# AetherMesh_interface_to_TI_SmartRF06EB_M.net
KiCad netlist of a schematic drawn in EAGLE
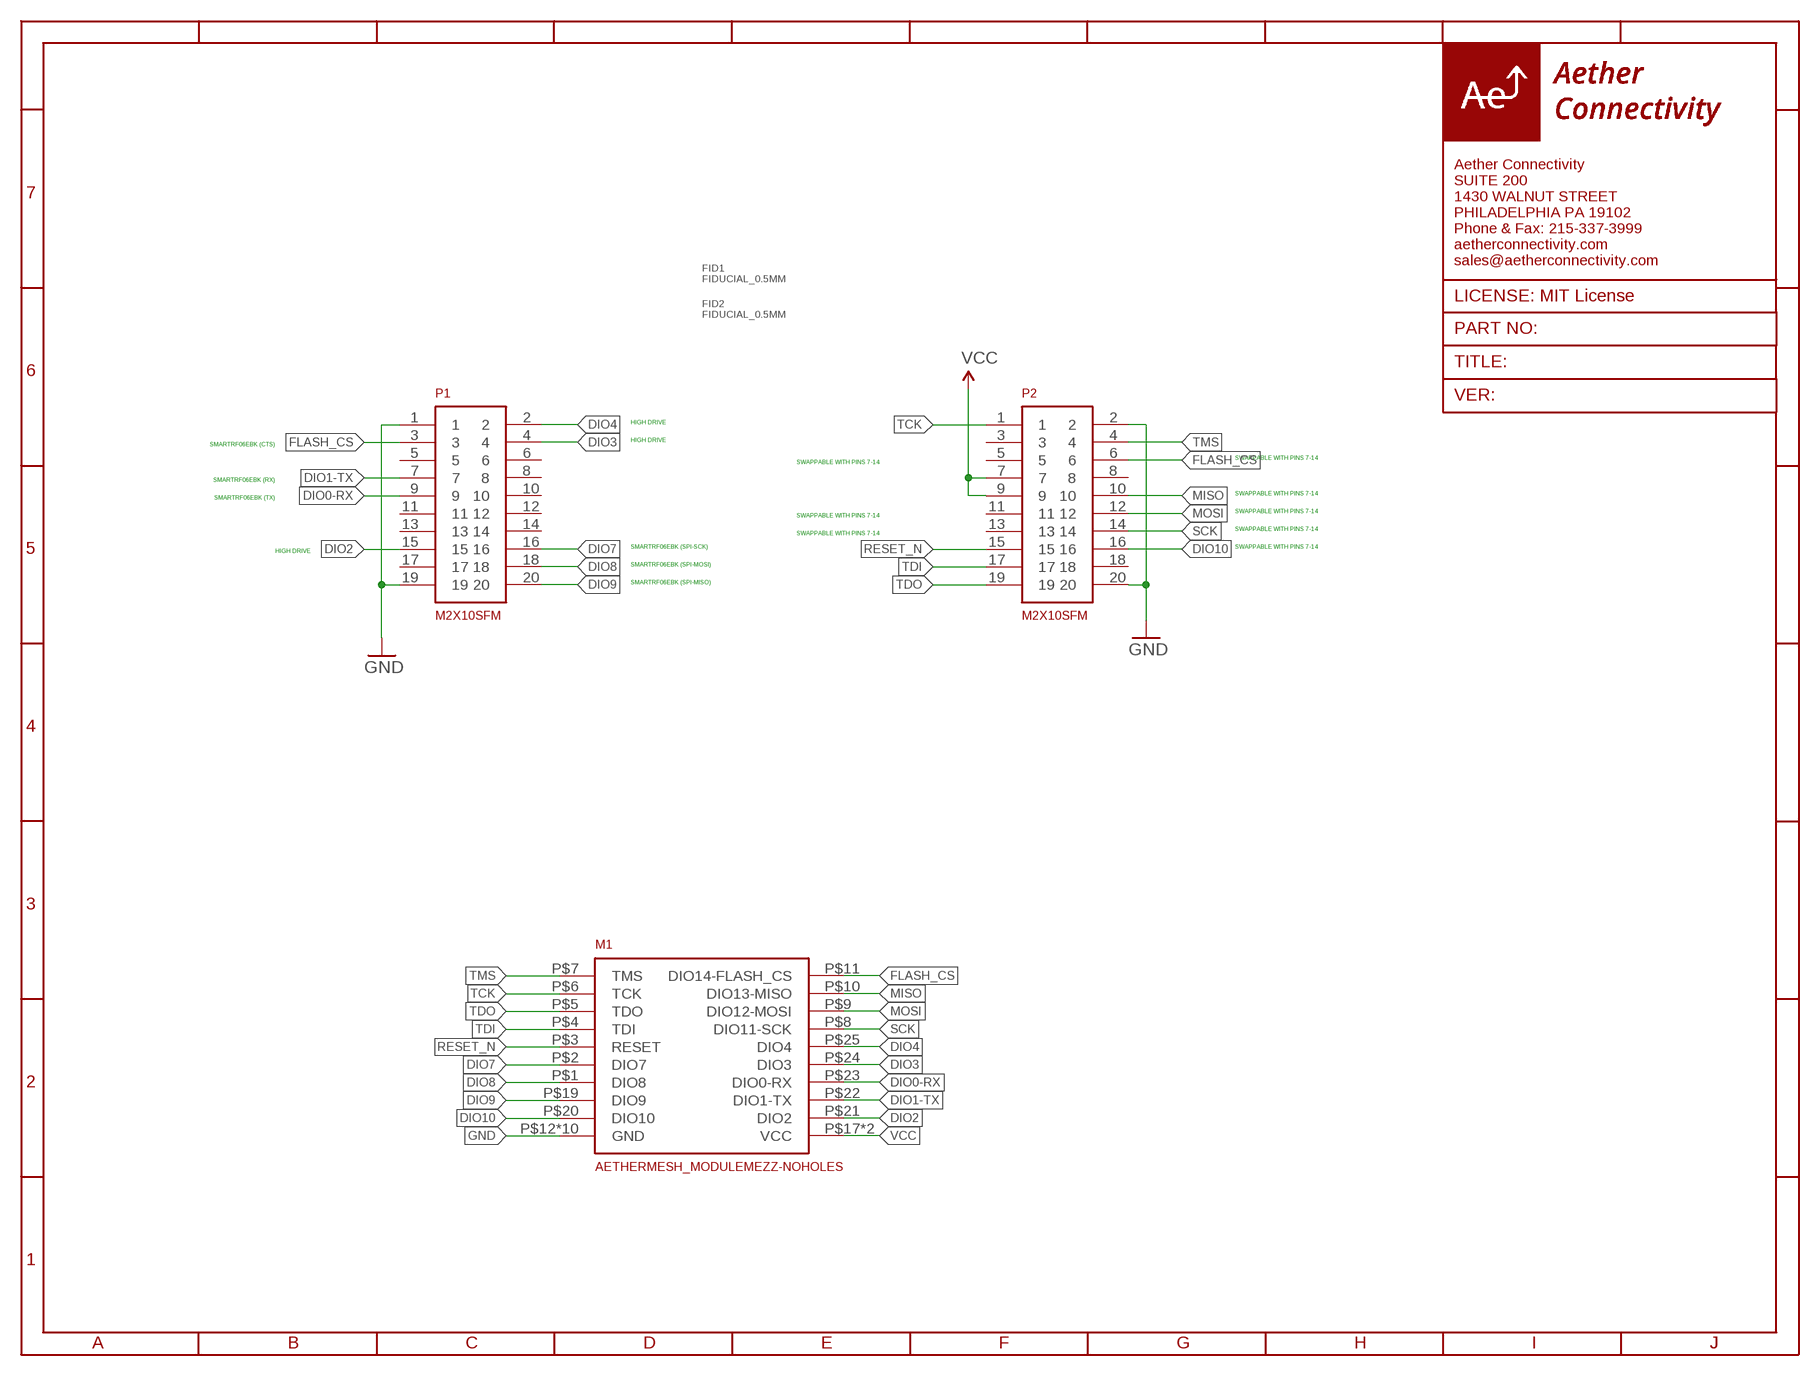
[diagram p0: schematic, sheet 1]

(export (version "E")
  (design (tool "Eeschema 10.0.6"))
  (components
    (comp (ref "FID1")
      (value "FIDUCIAL_0.5MM")
      (footprint "eagle-import:FIDUCIAL_0.5MM")
      (libsource (lib "eagle-import") (part "FIDUCIAL_0.5MM"))
    )
    (comp (ref "FID2")
      (value "FIDUCIAL_0.5MM")
      (footprint "eagle-import:FIDUCIAL_0.5MM")
      (libsource (lib "eagle-import") (part "FIDUCIAL_0.5MM"))
    )
    (comp (ref "M1")
      (value "AETHERMESH_MODULEMEZZ-NOHOLES")
      (footprint "eagle-import:AETHERMESH_MEZZ_MOUNT_NOHOLES")
      (libsource (lib "eagle-import") (part "AETHERMESH_MODULEMEZZ-NOHOLES"))
    )
    (comp (ref "P1")
      (value "M2X10SFM")
      (footprint "eagle-import:2X10_SFM-110-02-S-D-A-K-TR")
      (libsource (lib "eagle-import") (part "M2X10SFM"))
    )
    (comp (ref "P2")
      (value "M2X10SFM")
      (footprint "eagle-import:2X10_SFM-110-02-S-D-A-K-TR")
      (libsource (lib "eagle-import") (part "M2X10SFM"))
    )
  )
  (nets
    (net (code "1") (name "DIO0-RX") (class "Default")
      (node (ref "M1") (pin "P$23") (pinfunction "DIO0-RX_P$23") (pintype "bidirectional"))
      (node (ref "P1") (pin "9") (pinfunction "9_9") (pintype "bidirectional"))
    )
    (net (code "2") (name "DIO1-TX") (class "Default")
      (node (ref "M1") (pin "P$22") (pinfunction "DIO1-TX_P$22") (pintype "bidirectional"))
      (node (ref "P1") (pin "7") (pinfunction "7_7") (pintype "bidirectional"))
    )
    (net (code "3") (name "DIO2") (class "Default")
      (node (ref "M1") (pin "P$21") (pinfunction "DIO2_P$21") (pintype "bidirectional"))
      (node (ref "P1") (pin "15") (pinfunction "15_15") (pintype "bidirectional"))
    )
    (net (code "4") (name "DIO3") (class "Default")
      (node (ref "M1") (pin "P$24") (pinfunction "DIO3_P$24") (pintype "bidirectional"))
      (node (ref "P1") (pin "4") (pinfunction "4_4") (pintype "bidirectional"))
    )
    (net (code "5") (name "DIO4") (class "Default")
      (node (ref "M1") (pin "P$25") (pinfunction "DIO4_P$25") (pintype "bidirectional"))
      (node (ref "P1") (pin "2") (pinfunction "2_2") (pintype "bidirectional"))
    )
    (net (code "6") (name "DIO7") (class "Default")
      (node (ref "M1") (pin "P$2") (pinfunction "DIO7_P$2") (pintype "bidirectional"))
      (node (ref "P1") (pin "16") (pinfunction "16_16") (pintype "bidirectional"))
    )
    (net (code "7") (name "DIO8") (class "Default")
      (node (ref "M1") (pin "P$1") (pinfunction "DIO8_P$1") (pintype "bidirectional"))
      (node (ref "P1") (pin "18") (pinfunction "18_18") (pintype "bidirectional"))
    )
    (net (code "8") (name "DIO9") (class "Default")
      (node (ref "M1") (pin "P$19") (pinfunction "DIO9_P$19") (pintype "bidirectional"))
      (node (ref "P1") (pin "20") (pinfunction "20_20") (pintype "bidirectional"))
    )
    (net (code "9") (name "DIO10") (class "Default")
      (node (ref "M1") (pin "P$20") (pinfunction "DIO10_P$20") (pintype "bidirectional"))
      (node (ref "P2") (pin "16") (pinfunction "16_16") (pintype "bidirectional"))
    )
    (net (code "10") (name "FLASH_CS") (class "Default")
      (node (ref "M1") (pin "P$11") (pinfunction "DIO14-FLASH_CS_P$11") (pintype "bidirectional"))
      (node (ref "P1") (pin "3") (pinfunction "3_3") (pintype "bidirectional"))
      (node (ref "P2") (pin "6") (pinfunction "6_6") (pintype "bidirectional"))
    )
    (net (code "11") (name "GND") (class "Default")
      (node (ref "M1") (pin "P$12") (pinfunction "GND_P$12") (pintype "bidirectional"))
      (node (ref "M1") (pin "P$13") (pinfunction "GND_P$13") (pintype "bidirectional"))
      (node (ref "M1") (pin "P$14") (pinfunction "GND_P$14") (pintype "bidirectional"))
      (node (ref "M1") (pin "P$15") (pinfunction "GND_P$15") (pintype "bidirectional"))
      (node (ref "M1") (pin "P$16") (pinfunction "GND_P$16") (pintype "bidirectional"))
      (node (ref "M1") (pin "P$26") (pinfunction "GND_P$26") (pintype "bidirectional"))
      (node (ref "M1") (pin "P$27") (pinfunction "GND_P$27") (pintype "bidirectional"))
      (node (ref "M1") (pin "P$28") (pinfunction "GND_P$28") (pintype "bidirectional"))
      (node (ref "M1") (pin "P$29") (pinfunction "GND_P$29") (pintype "bidirectional"))
      (node (ref "M1") (pin "P$30") (pinfunction "GND_P$30") (pintype "bidirectional"))
      (node (ref "P1") (pin "1") (pinfunction "1_1") (pintype "bidirectional"))
      (node (ref "P1") (pin "19") (pinfunction "19_19") (pintype "bidirectional"))
      (node (ref "P2") (pin "2") (pinfunction "2_2") (pintype "bidirectional"))
      (node (ref "P2") (pin "20") (pinfunction "20_20") (pintype "bidirectional"))
    )
    (net (code "12") (name "MISO") (class "Default")
      (node (ref "M1") (pin "P$10") (pinfunction "DIO13-MISO_P$10") (pintype "bidirectional"))
      (node (ref "P2") (pin "10") (pinfunction "10_10") (pintype "bidirectional"))
    )
    (net (code "13") (name "MOSI") (class "Default")
      (node (ref "M1") (pin "P$9") (pinfunction "DIO12-MOSI_P$9") (pintype "bidirectional"))
      (node (ref "P2") (pin "12") (pinfunction "12_12") (pintype "bidirectional"))
    )
    (net (code "14") (name "RESET_N") (class "Default")
      (node (ref "M1") (pin "P$3") (pinfunction "RESET_P$3") (pintype "bidirectional"))
      (node (ref "P2") (pin "15") (pinfunction "15_15") (pintype "bidirectional"))
    )
    (net (code "15") (name "SCK") (class "Default")
      (node (ref "M1") (pin "P$8") (pinfunction "DIO11-SCK_P$8") (pintype "bidirectional"))
      (node (ref "P2") (pin "14") (pinfunction "14_14") (pintype "bidirectional"))
    )
    (net (code "16") (name "TCK") (class "Default")
      (node (ref "M1") (pin "P$6") (pinfunction "TCK_P$6") (pintype "bidirectional"))
      (node (ref "P2") (pin "1") (pinfunction "1_1") (pintype "bidirectional"))
    )
    (net (code "17") (name "TDI") (class "Default")
      (node (ref "M1") (pin "P$4") (pinfunction "TDI_P$4") (pintype "bidirectional"))
      (node (ref "P2") (pin "17") (pinfunction "17_17") (pintype "bidirectional"))
    )
    (net (code "18") (name "TDO") (class "Default")
      (node (ref "M1") (pin "P$5") (pinfunction "TDO_P$5") (pintype "bidirectional"))
      (node (ref "P2") (pin "19") (pinfunction "19_19") (pintype "bidirectional"))
    )
    (net (code "19") (name "TMS") (class "Default")
      (node (ref "M1") (pin "P$7") (pinfunction "TMS_P$7") (pintype "bidirectional"))
      (node (ref "P2") (pin "4") (pinfunction "4_4") (pintype "bidirectional"))
    )
    (net (code "20") (name "VCC") (class "Default")
      (node (ref "M1") (pin "P$17") (pinfunction "VCC_P$17") (pintype "bidirectional"))
      (node (ref "M1") (pin "P$18") (pinfunction "VCC_P$18") (pintype "bidirectional"))
      (node (ref "P2") (pin "7") (pinfunction "7_7") (pintype "bidirectional"))
      (node (ref "P2") (pin "9") (pinfunction "9_9") (pintype "bidirectional"))
    )
    (net (code "21") (name "unconnected-(P1-Pad5)") (class "Default")
      (node (ref "P1") (pin "5") (pinfunction "5_5") (pintype "bidirectional"))
    )
    (net (code "22") (name "unconnected-(P1-Pad6)") (class "Default")
      (node (ref "P1") (pin "6") (pinfunction "6_6") (pintype "bidirectional"))
    )
    (net (code "23") (name "unconnected-(P1-Pad8)") (class "Default")
      (node (ref "P1") (pin "8") (pinfunction "8_8") (pintype "bidirectional"))
    )
    (net (code "24") (name "unconnected-(P1-Pad10)") (class "Default")
      (node (ref "P1") (pin "10") (pinfunction "10_10") (pintype "bidirectional"))
    )
    (net (code "25") (name "unconnected-(P1-Pad11)") (class "Default")
      (node (ref "P1") (pin "11") (pinfunction "11_11") (pintype "bidirectional"))
    )
    (net (code "26") (name "unconnected-(P1-Pad12)") (class "Default")
      (node (ref "P1") (pin "12") (pinfunction "12_12") (pintype "bidirectional"))
    )
    (net (code "27") (name "unconnected-(P1-Pad13)") (class "Default")
      (node (ref "P1") (pin "13") (pinfunction "13_13") (pintype "bidirectional"))
    )
    (net (code "28") (name "unconnected-(P1-Pad14)") (class "Default")
      (node (ref "P1") (pin "14") (pinfunction "14_14") (pintype "bidirectional"))
    )
    (net (code "29") (name "unconnected-(P1-Pad17)") (class "Default")
      (node (ref "P1") (pin "17") (pinfunction "17_17") (pintype "bidirectional"))
    )
    (net (code "30") (name "unconnected-(P2-Pad3)") (class "Default")
      (node (ref "P2") (pin "3") (pinfunction "3_3") (pintype "bidirectional"))
    )
    (net (code "31") (name "unconnected-(P2-Pad5)") (class "Default")
      (node (ref "P2") (pin "5") (pinfunction "5_5") (pintype "bidirectional"))
    )
    (net (code "32") (name "unconnected-(P2-Pad8)") (class "Default")
      (node (ref "P2") (pin "8") (pinfunction "8_8") (pintype "bidirectional"))
    )
    (net (code "33") (name "unconnected-(P2-Pad11)") (class "Default")
      (node (ref "P2") (pin "11") (pinfunction "11_11") (pintype "bidirectional"))
    )
    (net (code "34") (name "unconnected-(P2-Pad13)") (class "Default")
      (node (ref "P2") (pin "13") (pinfunction "13_13") (pintype "bidirectional"))
    )
    (net (code "35") (name "unconnected-(P2-Pad18)") (class "Default")
      (node (ref "P2") (pin "18") (pinfunction "18_18") (pintype "bidirectional"))
    )
  )
)
